# emi_filter_ch1_a.net
KiCad netlist of a schematic drawn in Altium Designer
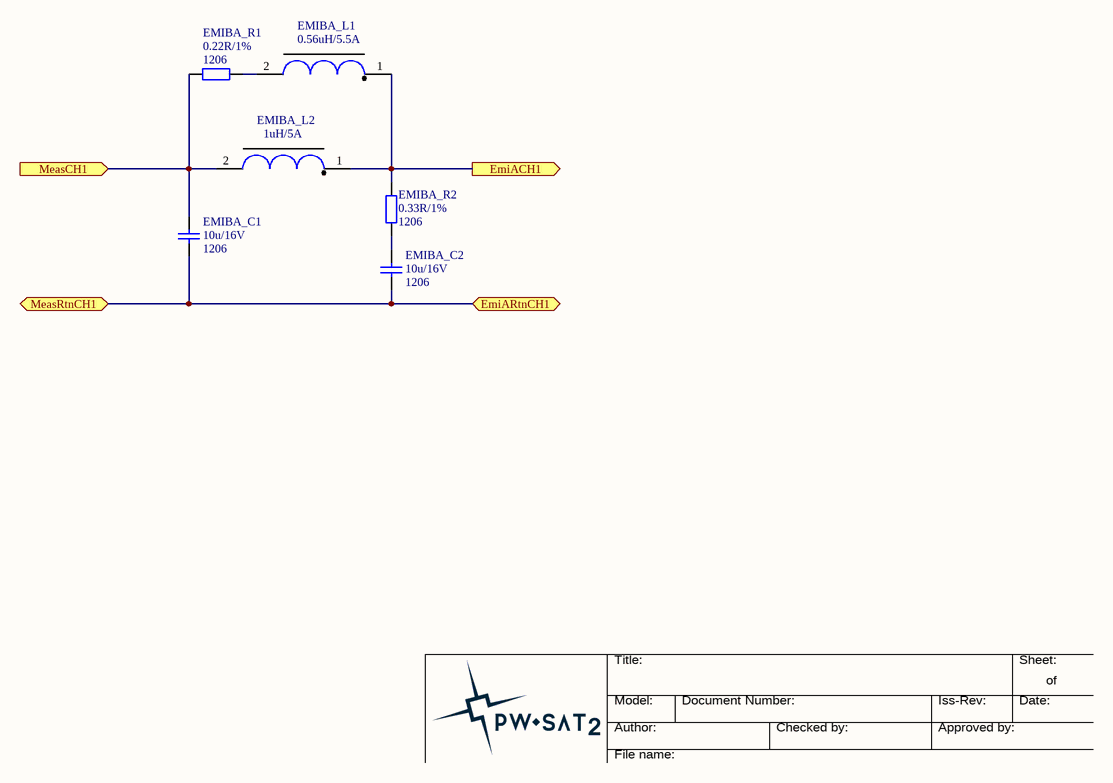
[diagram p0: emi_filter_ch1_a.SchDoc]

(export (version "E")
  (design (tool "Eeschema 10.0.6"))
  (components
    (comp (ref "EMIBA_C1")
      (value "10u/16V")
      (footprint "SMD_Capacitor_1206")
      (description "Ceramic Cap Kemet COTS 10u/16V X7R 1206")
      (fields
        (field (name "MANUFACTURERPARTNUMBER") "C1206T106K4RACTU")
        (field (name "MANUFACTURER") "Kemet")
        (field (name "PACKGE") "1206")
      )
      (libsource (lib "capacitors") (part "Cer_C1206T106K4RACTU"))
    )
    (comp (ref "EMIBA_C2")
      (value "10u/16V")
      (footprint "SMD_Capacitor_1206")
      (description "Ceramic Cap Kemet COTS 10u/16V X7R 1206")
      (fields
        (field (name "MANUFACTURERPARTNUMBER") "C1206T106K4RACTU")
        (field (name "MANUFACTURER") "Kemet")
        (field (name "PACKGE") "1206")
      )
      (libsource (lib "capacitors") (part "Cer_C1206T106K4RACTU"))
    )
    (comp (ref "EMIBA_L1")
      (value "0.56uH/5.5A")
      (footprint "Vishay_IHLP1212")
      (description "Vishay IHLP1212 Inductor, L=0.56uH, Irise40deg=5.5A, ESR=16mR, SRF=1MHz.")
      (fields
        (field (name "MANUFACTURER") "Vishay")
        (field (name "MANUFACTURERPARTNUMBER") "IHLP1212BZERR56M11")
      )
      (libsource (lib "inductors") (part "IHLP1212BZERR56M11"))
    )
    (comp (ref "EMIBA_L2")
      (value "1uH/5A")
      (footprint "Vishay_IHLP1212")
      (description "Vishay IHLP1212 Inductor, L=1uH, Irise40deg=5A, ESR=20mR, SRF=1MHz.")
      (fields
        (field (name "MANUFACTURER") "Vishay")
        (field (name "MANUFACTURERPARTNUMBER") "IHLP1212BZER1R0M11")
      )
      (libsource (lib "inductors") (part "IHLP1212BZER1R0M11"))
    )
    (comp (ref "EMIBA_R1")
      (value "0.22R/1%")
      (footprint "SMD_Resistor_1206")
      (description "Panasonic Resistor 0.22R 1% 1206 330mW")
      (fields
        (field (name "MANUFACTURER") "Panasonic")
        (field (name "MANUFACTURERPARTNUMBER") "ERJ-8BQFR22V")
        (field (name "PACKAGE") "1206")
      )
      (libsource (lib "resistors") (part "ERJ-8BQFR22V"))
    )
    (comp (ref "EMIBA_R2")
      (value "0.33R/1%")
      (footprint "SMD_Resistor_1206")
      (description "Panasonic Resistor 0.33R 1% 1206 330mW")
      (fields
        (field (name "MANUFACTURER") "Panasonic")
        (field (name "MANUFACTURERPARTNUMBER") "ERJ-8BQFR33V")
        (field (name "PACKAGE") "1206")
      )
      (libsource (lib "resistors") (part "ERJ-8BQFR33V"))
    )
  )
  (nets
    (net (code "1") (name "/EmiACH1") (class "Default")
      (node (ref "EMIBA_L1") (pin "1") (pinfunction "1_1") (pintype "passive"))
      (node (ref "EMIBA_L2") (pin "1") (pinfunction "1_1") (pintype "passive"))
      (node (ref "EMIBA_R2") (pin "2") (pinfunction "2_2") (pintype "passive"))
    )
    (net (code "2") (name "/EmiARtnCH1") (class "Default")
      (node (ref "EMIBA_C1") (pin "2") (pinfunction "2_2") (pintype "passive"))
      (node (ref "EMIBA_C2") (pin "2") (pinfunction "2_2") (pintype "passive"))
    )
    (net (code "3") (name "/MeasCH1") (class "Default")
      (node (ref "EMIBA_C1") (pin "1") (pinfunction "1_1") (pintype "passive"))
      (node (ref "EMIBA_L2") (pin "2") (pinfunction "2_2") (pintype "passive"))
      (node (ref "EMIBA_R1") (pin "1") (pinfunction "1_1") (pintype "passive"))
    )
    (net (code "4") (name "Net-(EMIBA_C2-Pad1)") (class "Default")
      (node (ref "EMIBA_C2") (pin "1") (pinfunction "1_1") (pintype "passive"))
      (node (ref "EMIBA_R2") (pin "1") (pinfunction "1_1") (pintype "passive"))
    )
    (net (code "5") (name "Net-(EMIBA_L1-Pad2)") (class "Default")
      (node (ref "EMIBA_L1") (pin "2") (pinfunction "2_2") (pintype "passive"))
      (node (ref "EMIBA_R1") (pin "2") (pinfunction "2_2") (pintype "passive"))
    )
  )
)
